# Power.net
KiCad netlist of a schematic drawn in Altium Designer
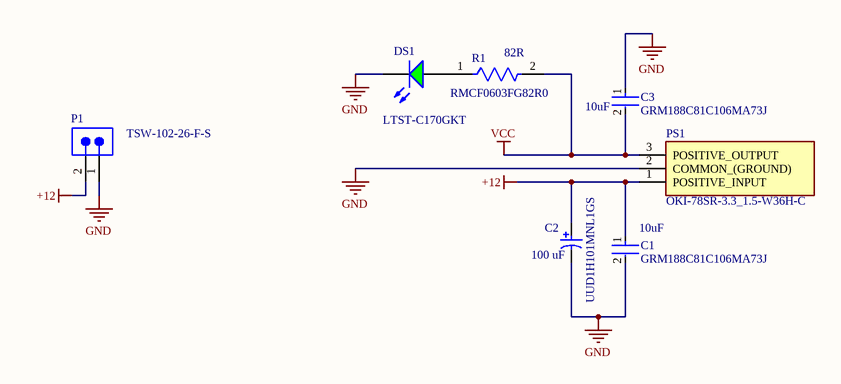
[diagram p0: Power.SchDoc]

(export (version "E")
  (design (tool "Eeschema 10.0.6"))
  (components
    (comp (ref "C1")
      (value "GRM188C81C106MA73J")
      (footprint "FP-GRM188-0_2-IPC_A")
      (description "Chip Multilayer Ceramic Capacitors for General Purpose, 0603, 10uF, X6S, 22%, 20%, 16V")
      (fields (field (name "TOLERANCE") "20%") (field (name "CAPACITANCE") "10uF"))
      (libsource (lib "Altium Content Vault") (part "11868f565c42a9108669ba33697ecf6"))
    )
    (comp (ref "C2")
      (value "UUD1H101MNL1GS")
      (footprint "NIC-CAPA2-8X10_V")
      (fields
        (field (name "MANUFACTURER") "Nichicon")
        (field (name "RATED CAPACITANCE") "100 uF")
        (field (name "TOLERANCE") "±20%")
      )
      (libsource (lib "Altium Content Vault") (part "NIC-CAP-P-2"))
    )
    (comp (ref "C3")
      (value "GRM188C81C106MA73J")
      (footprint "FP-GRM188-0_2-IPC_A")
      (description "Chip Multilayer Ceramic Capacitors for General Purpose, 0603, 10uF, X6S, 22%, 20%, 16V")
      (fields (field (name "TOLERANCE") "20%") (field (name "CAPACITANCE") "10uF"))
      (libsource (lib "Altium Content Vault") (part "11868f565c42a9108669ba33697ecf6"))
    )
    (comp (ref "DS1")
      (value "LTST-C170GKT")
      (footprint "LTST-C170GKT_V")
      (description "LED Uni-Color Green, 100 mW, 120 mA, -55 to 85 degC, 2-Pin SMD, RoHS, Tape and Reel")
      (fields (field (name "MANUFACTURER") "Lite-On"))
      (libsource (lib "Altium Content Vault") (part "LED-GREEN-AK-2"))
    )
    (comp (ref "P1")
      (value "TSW-102-26-F-S")
      (footprint "SMTC-TSW-102-26-XX-S")
      (description "0.025\" SQ Post Header, Through-hole, Vertical, -55 to 125 degC, 2.54 mm Pitch, 2-Pin, Male, RoHS")
      (fields (field (name "MANUFACTURER") "Samtec"))
      (libsource (lib "Altium Content Vault") (part "SMTC-TSW-102-X-X-S-X"))
    )
    (comp (ref "PS1")
      (value "OKI-78SR-3.3_1.5-W36H-C")
      (footprint "SamacSys:OKI78SR3315W36HC")
      (description "Power Supply")
      (fields
        (field (name "MANUFACTURER_PART_NUMBER") "OKI-78SR-3.3/1.5-W36H-C")
        (field (name "MOUSER PART NUMBER") "580-OKI78SR3.31.5WHC")
      )
      (libsource (lib "SamacSys") (part "OKI-78SR-3.3_1.5-W36H-C"))
    )
    (comp (ref "R1")
      (value "RMCF0603FG82R0")
      (footprint "FP-RMCF0603-IPC_A")
      (description "82Ω ±1% 0.1W 0603 Thick Film Chip Resistor AEC-Q200 compliant")
      (fields (field (name "ALTIUM_VALUE") "82R"))
      (libsource (lib "Altium Content Vault") (part "1029c3af85768c4190bb7ad29bc67b5"))
    )
  )
  (nets
    (net (code "1") (name "+12") (class "Default")
      (node (ref "C1") (pin "1") (pinfunction "1_1") (pintype "passive"))
      (node (ref "C2") (pin "1") (pinfunction "1_1") (pintype "passive"))
      (node (ref "P1") (pin "2") (pinfunction "2_2") (pintype "passive"))
      (node (ref "PS1") (pin "1") (pinfunction "POSITIVE_INPUT_1") (pintype "passive"))
    )
    (net (code "2") (name "GND") (class "Default")
      (node (ref "C1") (pin "2") (pinfunction "2_2") (pintype "passive"))
      (node (ref "C2") (pin "2") (pinfunction "2_2") (pintype "passive"))
      (node (ref "C3") (pin "1") (pinfunction "1_1") (pintype "passive"))
      (node (ref "DS1") (pin "2") (pinfunction "K_2") (pintype "passive"))
      (node (ref "P1") (pin "1") (pinfunction "1_1") (pintype "passive"))
      (node (ref "PS1") (pin "2") (pinfunction "COMMON_(GROUND)_2") (pintype "passive"))
    )
    (net (code "3") (name "Net-(DS1-A)") (class "Default")
      (node (ref "DS1") (pin "1") (pinfunction "A_1") (pintype "passive"))
      (node (ref "R1") (pin "1") (pinfunction "1_1") (pintype "passive"))
    )
    (net (code "4") (name "VCC") (class "Default")
      (node (ref "C3") (pin "2") (pinfunction "2_2") (pintype "passive"))
      (node (ref "PS1") (pin "3") (pinfunction "POSITIVE_OUTPUT_3") (pintype "passive"))
      (node (ref "R1") (pin "2") (pinfunction "2_2") (pintype "passive"))
    )
  )
)
